# H3BR6_Hardware.net
KiCad netlist of a schematic drawn in EAGLE
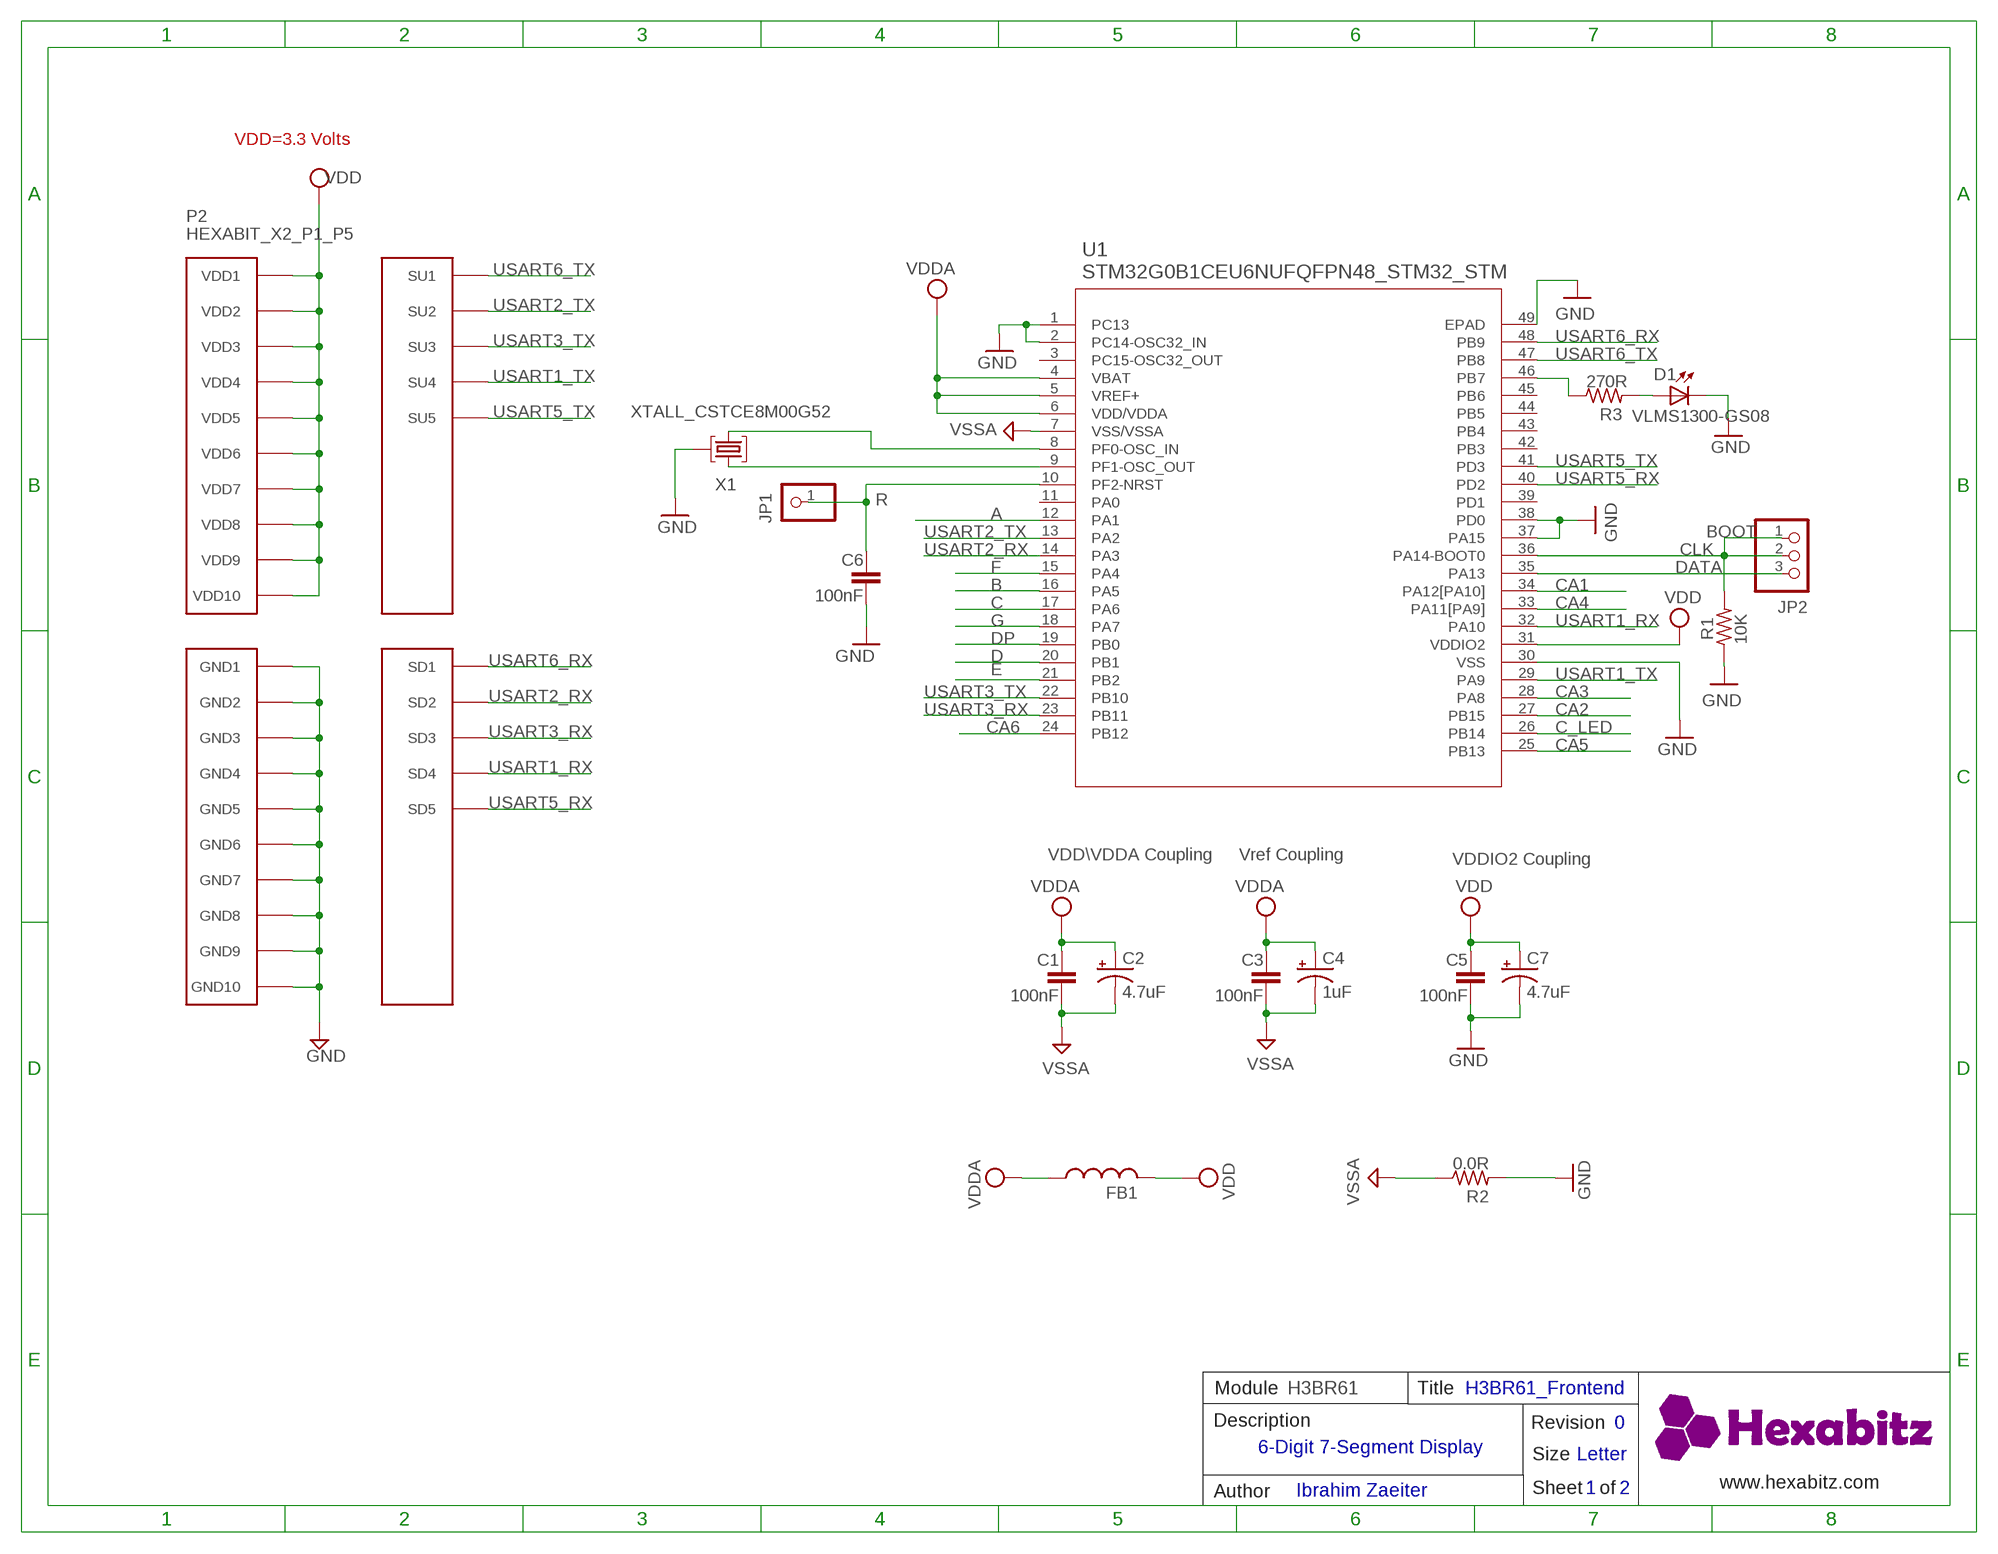
[diagram p0: schematic, sheet 1]
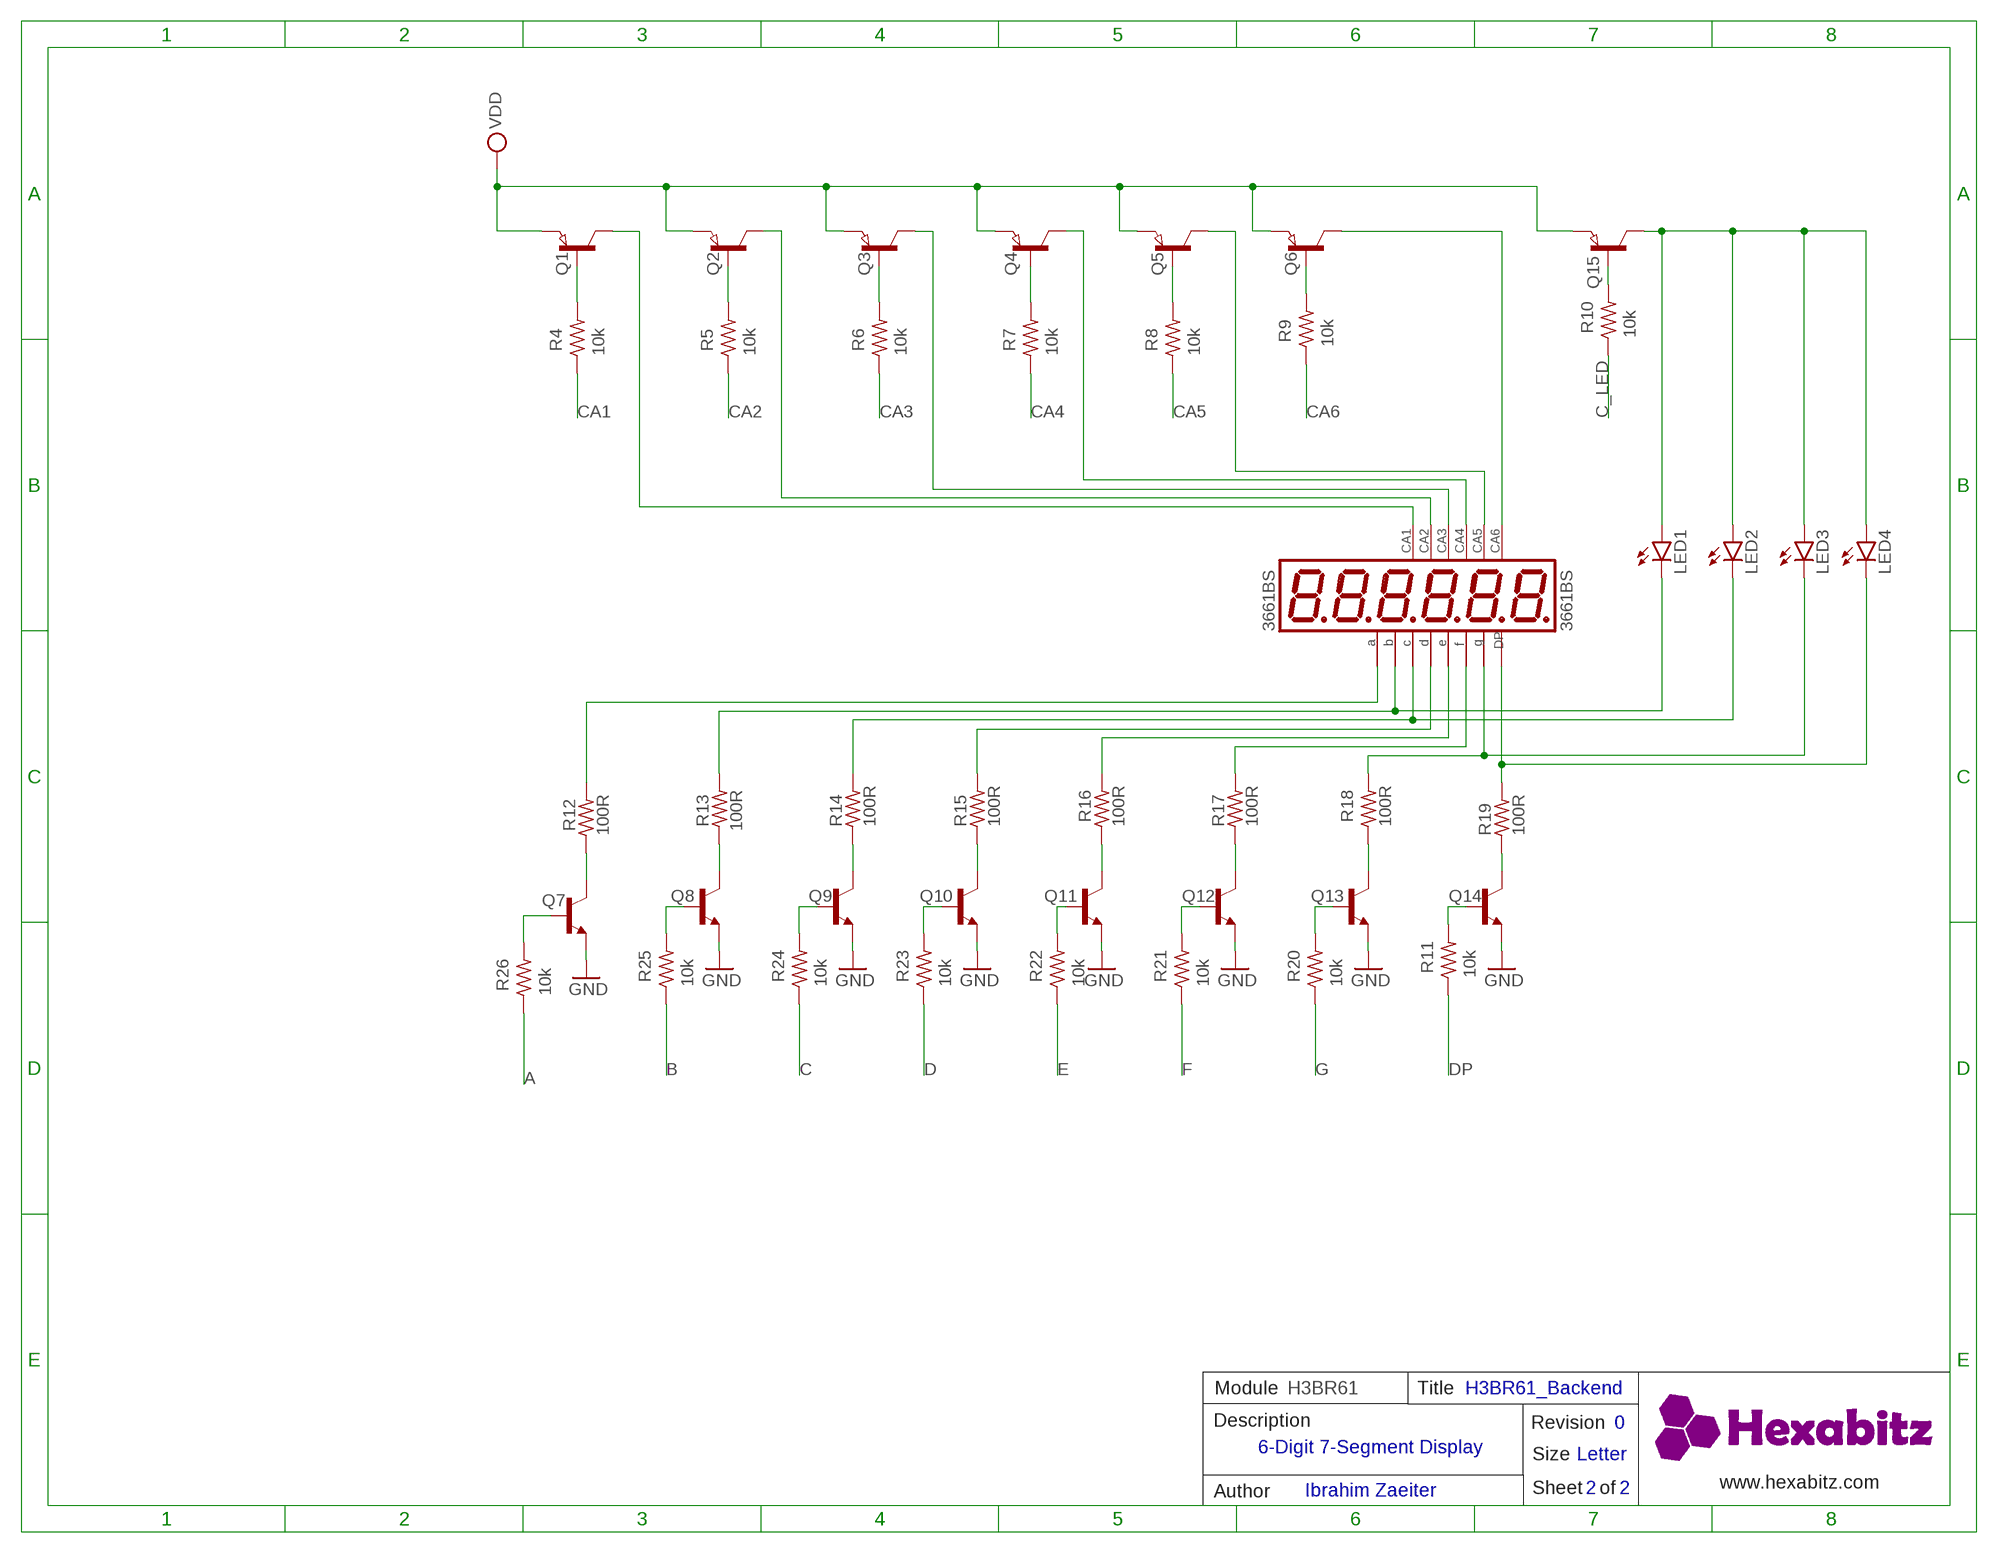
[diagram p1: schematic, sheet 2]

(export (version "E")
  (design (tool "Eeschema 10.0.6"))
  (components
    (comp (ref "3661BS")
      (value "3661BS")
      (footprint "eagle-import:3661BS")
      (libsource (lib "eagle-import") (part "3661BS"))
    )
    (comp (ref "LED1")
      (value "LED3MM")
      (footprint "eagle-import:LED3MM")
      (libsource (lib "eagle-import") (part "LED3MM"))
    )
    (comp (ref "LED2")
      (value "LED3MM")
      (footprint "eagle-import:LED3MM")
      (libsource (lib "eagle-import") (part "LED3MM"))
    )
    (comp (ref "LED3")
      (value "LED3MM")
      (footprint "eagle-import:LED3MM")
      (libsource (lib "eagle-import") (part "LED3MM"))
    )
    (comp (ref "LED4")
      (value "LED3MM")
      (footprint "eagle-import:LED3MM")
      (libsource (lib "eagle-import") (part "LED3MM"))
    )
    (comp (ref "Q1")
      (value "SEMICON-SMD-IPC_PNP-TRANSISTOR_SOT23")
      (footprint "eagle-import:SEMICON-SMD-IPC_SOT23")
      (libsource (lib "eagle-import") (part "SEMICON-SMD-IPC_PNP-TRANSISTOR_SOT23"))
    )
    (comp (ref "Q2")
      (value "SEMICON-SMD-IPC_PNP-TRANSISTOR_SOT23")
      (footprint "eagle-import:SEMICON-SMD-IPC_SOT23")
      (libsource (lib "eagle-import") (part "SEMICON-SMD-IPC_PNP-TRANSISTOR_SOT23"))
    )
    (comp (ref "Q3")
      (value "SEMICON-SMD-IPC_PNP-TRANSISTOR_SOT23")
      (footprint "eagle-import:SEMICON-SMD-IPC_SOT23")
      (libsource (lib "eagle-import") (part "SEMICON-SMD-IPC_PNP-TRANSISTOR_SOT23"))
    )
    (comp (ref "Q4")
      (value "SEMICON-SMD-IPC_PNP-TRANSISTOR_SOT23")
      (footprint "eagle-import:SEMICON-SMD-IPC_SOT23")
      (libsource (lib "eagle-import") (part "SEMICON-SMD-IPC_PNP-TRANSISTOR_SOT23"))
    )
    (comp (ref "Q5")
      (value "SEMICON-SMD-IPC_PNP-TRANSISTOR_SOT23")
      (footprint "eagle-import:SEMICON-SMD-IPC_SOT23")
      (libsource (lib "eagle-import") (part "SEMICON-SMD-IPC_PNP-TRANSISTOR_SOT23"))
    )
    (comp (ref "Q6")
      (value "SEMICON-SMD-IPC_PNP-TRANSISTOR_SOT23")
      (footprint "eagle-import:SEMICON-SMD-IPC_SOT23")
      (libsource (lib "eagle-import") (part "SEMICON-SMD-IPC_PNP-TRANSISTOR_SOT23"))
    )
    (comp (ref "Q7")
      (value "MMBT3904LT1")
      (footprint "eagle-import:MMBT3904LT1")
      (libsource (lib "eagle-import") (part "MMBT3904LT1"))
    )
    (comp (ref "Q8")
      (value "MMBT3904LT1")
      (footprint "eagle-import:MMBT3904LT1")
      (libsource (lib "eagle-import") (part "MMBT3904LT1"))
    )
    (comp (ref "Q9")
      (value "MMBT3904LT1")
      (footprint "eagle-import:MMBT3904LT1")
      (libsource (lib "eagle-import") (part "MMBT3904LT1"))
    )
    (comp (ref "Q10")
      (value "MMBT3904LT1")
      (footprint "eagle-import:MMBT3904LT1")
      (libsource (lib "eagle-import") (part "MMBT3904LT1"))
    )
    (comp (ref "Q11")
      (value "MMBT3904LT1")
      (footprint "eagle-import:MMBT3904LT1")
      (libsource (lib "eagle-import") (part "MMBT3904LT1"))
    )
    (comp (ref "Q12")
      (value "MMBT3904LT1")
      (footprint "eagle-import:MMBT3904LT1")
      (libsource (lib "eagle-import") (part "MMBT3904LT1"))
    )
    (comp (ref "Q13")
      (value "MMBT3904LT1")
      (footprint "eagle-import:MMBT3904LT1")
      (libsource (lib "eagle-import") (part "MMBT3904LT1"))
    )
    (comp (ref "Q14")
      (value "MMBT3904LT1")
      (footprint "eagle-import:MMBT3904LT1")
      (libsource (lib "eagle-import") (part "MMBT3904LT1"))
    )
    (comp (ref "Q15")
      (value "SEMICON-SMD-IPC_PNP-TRANSISTOR_SOT23")
      (footprint "eagle-import:SEMICON-SMD-IPC_SOT23")
      (libsource (lib "eagle-import") (part "SEMICON-SMD-IPC_PNP-TRANSISTOR_SOT23"))
    )
    (comp (ref "R4")
      (value "10k")
      (footprint "eagle-import:R-0603")
      (libsource (lib "eagle-import") (part "R-0603"))
    )
    (comp (ref "R5")
      (value "10k")
      (footprint "eagle-import:R-0603")
      (libsource (lib "eagle-import") (part "R-0603"))
    )
    (comp (ref "R6")
      (value "10k")
      (footprint "eagle-import:R-0603")
      (libsource (lib "eagle-import") (part "R-0603"))
    )
    (comp (ref "R7")
      (value "10k")
      (footprint "eagle-import:R-0603")
      (libsource (lib "eagle-import") (part "R-0603"))
    )
    (comp (ref "R8")
      (value "10k")
      (footprint "eagle-import:R-0603")
      (libsource (lib "eagle-import") (part "R-0603"))
    )
    (comp (ref "R9")
      (value "10k")
      (footprint "eagle-import:R-0603")
      (libsource (lib "eagle-import") (part "R-0603"))
    )
    (comp (ref "R10")
      (value "10k")
      (footprint "eagle-import:R-0603")
      (libsource (lib "eagle-import") (part "R-0603"))
    )
    (comp (ref "R11")
      (value "10k")
      (footprint "eagle-import:R-0603")
      (libsource (lib "eagle-import") (part "R-0603"))
    )
    (comp (ref "R12")
      (value "100R")
      (footprint "eagle-import:R-0603")
      (libsource (lib "eagle-import") (part "R-0603"))
    )
    (comp (ref "R13")
      (value "100R")
      (footprint "eagle-import:R-0603")
      (libsource (lib "eagle-import") (part "R-0603"))
    )
    (comp (ref "R14")
      (value "100R")
      (footprint "eagle-import:R-0603")
      (libsource (lib "eagle-import") (part "R-0603"))
    )
    (comp (ref "R15")
      (value "100R")
      (footprint "eagle-import:R-0603")
      (libsource (lib "eagle-import") (part "R-0603"))
    )
    (comp (ref "R16")
      (value "100R")
      (footprint "eagle-import:R-0603")
      (libsource (lib "eagle-import") (part "R-0603"))
    )
    (comp (ref "R17")
      (value "100R")
      (footprint "eagle-import:R-0603")
      (libsource (lib "eagle-import") (part "R-0603"))
    )
    (comp (ref "R18")
      (value "100R")
      (footprint "eagle-import:R-0603")
      (libsource (lib "eagle-import") (part "R-0603"))
    )
    (comp (ref "R19")
      (value "100R")
      (footprint "eagle-import:R-0603")
      (libsource (lib "eagle-import") (part "R-0603"))
    )
    (comp (ref "R20")
      (value "10k")
      (footprint "eagle-import:R-0603")
      (libsource (lib "eagle-import") (part "R-0603"))
    )
    (comp (ref "R21")
      (value "10k")
      (footprint "eagle-import:R-0603")
      (libsource (lib "eagle-import") (part "R-0603"))
    )
    (comp (ref "R22")
      (value "10k")
      (footprint "eagle-import:R-0603")
      (libsource (lib "eagle-import") (part "R-0603"))
    )
    (comp (ref "R23")
      (value "10k")
      (footprint "eagle-import:R-0603")
      (libsource (lib "eagle-import") (part "R-0603"))
    )
    (comp (ref "R24")
      (value "10k")
      (footprint "eagle-import:R-0603")
      (libsource (lib "eagle-import") (part "R-0603"))
    )
    (comp (ref "R25")
      (value "10k")
      (footprint "eagle-import:R-0603")
      (libsource (lib "eagle-import") (part "R-0603"))
    )
    (comp (ref "R26")
      (value "10k")
      (footprint "eagle-import:R-0603")
      (libsource (lib "eagle-import") (part "R-0603"))
    )
    (comp (ref "C1")
      (value "100nF")
      (footprint "eagle-import:C-0603")
      (libsource (lib "eagle-import") (part "C-0603"))
    )
    (comp (ref "C2")
      (value "4.7uF")
      (footprint "eagle-import:C-0805-POL")
      (libsource (lib "eagle-import") (part "C-0805-POL"))
    )
    (comp (ref "C3")
      (value "100nF")
      (footprint "eagle-import:C-0603")
      (libsource (lib "eagle-import") (part "C-0603"))
    )
    (comp (ref "C4")
      (value "1uF")
      (footprint "eagle-import:C-0805-POL")
      (libsource (lib "eagle-import") (part "C-0805-POL"))
    )
    (comp (ref "C5")
      (value "100nF")
      (footprint "eagle-import:C-0603")
      (libsource (lib "eagle-import") (part "C-0603"))
    )
    (comp (ref "C6")
      (value "100nF")
      (footprint "eagle-import:C-0603")
      (libsource (lib "eagle-import") (part "C-0603"))
    )
    (comp (ref "C7")
      (value "4.7uF")
      (footprint "eagle-import:C-0805-POL")
      (libsource (lib "eagle-import") (part "C-0805-POL"))
    )
    (comp (ref "D1")
      (value "VLMS1300-GS08")
      (footprint "eagle-import:VLMS1300-GS08")
      (fields
        (field (name "MFN") "Vishay")
        (field (name "MPN") "VLMS1300-GS08")
        (field (name "OCTOPART_URL") "https://octopart.com/vlms1300-gs08-vishay-21709201?r=sp&s=_gcP4_q8T1SC6PJQPTQ9yA")
      )
      (libsource (lib "eagle-import") (part "VLMS1300-GS08"))
    )
    (comp (ref "FB1")
      (value "FB-0603")
      (footprint "eagle-import:FB-0603")
      (libsource (lib "eagle-import") (part "FB-0603"))
    )
    (comp (ref "JP1")
      (value "R")
      (footprint "eagle-import:1X01")
      (fields (field (name "MPN") "87227-1"))
      (libsource (lib "eagle-import") (part "PINHD-1X1"))
    )
    (comp (ref "JP2")
      (value "PINHD-1X3")
      (footprint "eagle-import:1X03")
      (libsource (lib "eagle-import") (part "PINHD-1X3"))
    )
    (comp (ref "P2")
      (value "HEXABIT_X2_P1_P5")
      (footprint "eagle-import:HEXABIT_17.32_X2_P1_P5")
      (libsource (lib "eagle-import") (part "HEXABIT_X2_P1_P5"))
    )
    (comp (ref "R1")
      (value "10K")
      (footprint "eagle-import:R-0603")
      (libsource (lib "eagle-import") (part "R-0603"))
    )
    (comp (ref "R2")
      (value "0.0R")
      (footprint "eagle-import:R-0603")
      (libsource (lib "eagle-import") (part "R-0603"))
    )
    (comp (ref "R3")
      (value "270R")
      (footprint "eagle-import:R-0603")
      (libsource (lib "eagle-import") (part "R-0603"))
    )
    (comp (ref "U1")
      (value "STM32G0B1CEU6NUFQFPN48_STM32_STM")
      (footprint "eagle-import:UFQFPN48_STM32_STM")
      (fields
        (field (name "MPN") "STM32G0B1CEU6N")
        (field (name "COPYRIGHT") "Copyright (C) 2022 Ultra Librarian. All rights reserved.")
      )
      (libsource (lib "eagle-import") (part "STM32G0B1CEU6NUFQFPN48_STM32_STM"))
    )
    (comp (ref "X1")
      (value "XTALL_CSTCE8M00G52")
      (footprint "eagle-import:XTALL_CSTCE8M00G52")
      (fields (field (name "MPN") "CSTCE8M00G52Z-R0"))
      (libsource (lib "eagle-import") (part "XTALL_CSTCE8M00G52"))
    )
  )
  (nets
    (net (code "1") (name "A") (class "Default")
      (node (ref "R26") (pin "1") (pinfunction "1_1") (pintype "passive"))
      (node (ref "U1") (pin "12") (pinfunction "PA1_12") (pintype "bidirectional"))
    )
    (net (code "2") (name "B") (class "Default")
      (node (ref "R25") (pin "1") (pinfunction "1_1") (pintype "passive"))
      (node (ref "U1") (pin "16") (pinfunction "PA5_16") (pintype "bidirectional"))
    )
    (net (code "3") (name "C") (class "Default")
      (node (ref "R24") (pin "1") (pinfunction "1_1") (pintype "passive"))
      (node (ref "U1") (pin "17") (pinfunction "PA6_17") (pintype "bidirectional"))
    )
    (net (code "4") (name "CA1") (class "Default")
      (node (ref "R4") (pin "1") (pinfunction "1_1") (pintype "passive"))
      (node (ref "U1") (pin "34") (pinfunction "PA12[PA10]_34") (pintype "bidirectional"))
    )
    (net (code "5") (name "CA2") (class "Default")
      (node (ref "R5") (pin "1") (pinfunction "1_1") (pintype "passive"))
      (node (ref "U1") (pin "27") (pinfunction "PB15_27") (pintype "bidirectional"))
    )
    (net (code "6") (name "CA3") (class "Default")
      (node (ref "R6") (pin "1") (pinfunction "1_1") (pintype "passive"))
      (node (ref "U1") (pin "28") (pinfunction "PA8_28") (pintype "bidirectional"))
    )
    (net (code "7") (name "CA4") (class "Default")
      (node (ref "R7") (pin "1") (pinfunction "1_1") (pintype "passive"))
      (node (ref "U1") (pin "33") (pinfunction "PA11[PA9]_33") (pintype "bidirectional"))
    )
    (net (code "8") (name "CA5") (class "Default")
      (node (ref "R8") (pin "1") (pinfunction "1_1") (pintype "passive"))
      (node (ref "U1") (pin "25") (pinfunction "PB13_25") (pintype "bidirectional"))
    )
    (net (code "9") (name "CA6") (class "Default")
      (node (ref "R9") (pin "1") (pinfunction "1_1") (pintype "passive"))
      (node (ref "U1") (pin "24") (pinfunction "PB12_24") (pintype "bidirectional"))
    )
    (net (code "10") (name "CLK") (class "Default")
      (node (ref "JP2") (pin "1") (pinfunction "1_1") (pintype "passive"))
      (node (ref "JP2") (pin "2") (pinfunction "2_2") (pintype "passive"))
      (node (ref "R1") (pin "2") (pinfunction "2_2") (pintype "passive"))
      (node (ref "U1") (pin "36") (pinfunction "PA14-BOOT0_36") (pintype "bidirectional"))
    )
    (net (code "11") (name "C_LED") (class "Default")
      (node (ref "R10") (pin "1") (pinfunction "1_1") (pintype "passive"))
      (node (ref "U1") (pin "26") (pinfunction "PB14_26") (pintype "bidirectional"))
    )
    (net (code "12") (name "D") (class "Default")
      (node (ref "R23") (pin "1") (pinfunction "1_1") (pintype "passive"))
      (node (ref "U1") (pin "20") (pinfunction "PB1_20") (pintype "bidirectional"))
    )
    (net (code "13") (name "DATA") (class "Default")
      (node (ref "JP2") (pin "3") (pinfunction "3_3") (pintype "passive"))
      (node (ref "U1") (pin "35") (pinfunction "PA13_35") (pintype "bidirectional"))
    )
    (net (code "14") (name "DP") (class "Default")
      (node (ref "R11") (pin "1") (pinfunction "1_1") (pintype "passive"))
      (node (ref "U1") (pin "19") (pinfunction "PB0_19") (pintype "bidirectional"))
    )
    (net (code "15") (name "E") (class "Default")
      (node (ref "R22") (pin "1") (pinfunction "1_1") (pintype "passive"))
      (node (ref "U1") (pin "21") (pinfunction "PB2_21") (pintype "bidirectional"))
    )
    (net (code "16") (name "F") (class "Default")
      (node (ref "R21") (pin "1") (pinfunction "1_1") (pintype "passive"))
      (node (ref "U1") (pin "15") (pinfunction "PA4_15") (pintype "bidirectional"))
    )
    (net (code "17") (name "G") (class "Default")
      (node (ref "R20") (pin "1") (pinfunction "1_1") (pintype "passive"))
      (node (ref "U1") (pin "18") (pinfunction "PA7_18") (pintype "bidirectional"))
    )
    (net (code "18") (name "GND") (class "Default")
      (node (ref "C5") (pin "2") (pinfunction "2_2") (pintype "passive"))
      (node (ref "C6") (pin "2") (pinfunction "2_2") (pintype "passive"))
      (node (ref "C7") (pin "2") (pinfunction "-_2") (pintype "passive"))
      (node (ref "D1") (pin "C") (pinfunction "C_C") (pintype "passive"))
      (node (ref "P2") (pin "PAD_PD11") (pinfunction "GND1_PAD_PD11") (pintype "power_in"))
      (node (ref "P2") (pin "PAD_PD12") (pinfunction "GND2_PAD_PD12") (pintype "power_in"))
      (node (ref "P2") (pin "PAD_PD13") (pinfunction "GND3_PAD_PD13") (pintype "power_in"))
      (node (ref "P2") (pin "PAD_PD14") (pinfunction "GND4_PAD_PD14") (pintype "power_in"))
      (node (ref "P2") (pin "PAD_PD15") (pinfunction "GND5_PAD_PD15") (pintype "power_in"))
      (node (ref "P2") (pin "PAD_PD16") (pinfunction "GND6_PAD_PD16") (pintype "power_in"))
      (node (ref "P2") (pin "PAD_PD17") (pinfunction "GND7_PAD_PD17") (pintype "power_in"))
      (node (ref "P2") (pin "PAD_PD18") (pinfunction "GND8_PAD_PD18") (pintype "power_in"))
      (node (ref "P2") (pin "PAD_PD19") (pinfunction "GND9_PAD_PD19") (pintype "power_in"))
      (node (ref "P2") (pin "PAD_PD20") (pinfunction "GND10_PAD_PD20") (pintype "power_in"))
      (node (ref "Q10") (pin "2") (pinfunction "E_2") (pintype "passive"))
      (node (ref "Q11") (pin "2") (pinfunction "E_2") (pintype "passive"))
      (node (ref "Q12") (pin "2") (pinfunction "E_2") (pintype "passive"))
      (node (ref "Q13") (pin "2") (pinfunction "E_2") (pintype "passive"))
      (node (ref "Q14") (pin "2") (pinfunction "E_2") (pintype "passive"))
      (node (ref "Q7") (pin "2") (pinfunction "E_2") (pintype "passive"))
      (node (ref "Q8") (pin "2") (pinfunction "E_2") (pintype "passive"))
      (node (ref "Q9") (pin "2") (pinfunction "E_2") (pintype "passive"))
      (node (ref "R1") (pin "1") (pinfunction "1_1") (pintype "passive"))
      (node (ref "R2") (pin "2") (pinfunction "2_2") (pintype "passive"))
      (node (ref "U1") (pin "1") (pinfunction "PC13_1") (pintype "bidirectional"))
      (node (ref "U1") (pin "2") (pinfunction "PC14-OSC32_IN_2") (pintype "bidirectional"))
      (node (ref "U1") (pin "30") (pinfunction "VSS_30") (pintype "passive"))
      (node (ref "U1") (pin "37") (pinfunction "PA15_37") (pintype "bidirectional"))
      (node (ref "U1") (pin "38") (pinfunction "PD0_38") (pintype "bidirectional"))
      (node (ref "U1") (pin "49") (pinfunction "EPAD_49") (pintype "passive"))
      (node (ref "X1") (pin "P$2") (pinfunction "2_P$2") (pintype "passive"))
    )
    (net (code "19") (name "Net-(3661BS-A)") (class "Default")
      (node (ref "3661BS") (pin "13") (pinfunction "A_13") (pintype "passive"))
      (node (ref "R12") (pin "2") (pinfunction "2_2") (pintype "passive"))
    )
    (net (code "20") (name "Net-(3661BS-B)") (class "Default")
      (node (ref "3661BS") (pin "9") (pinfunction "B_9") (pintype "passive"))
      (node (ref "LED1") (pin "K") (pinfunction "C_K") (pintype "passive"))
      (node (ref "R13") (pin "2") (pinfunction "2_2") (pintype "passive"))
    )
    (net (code "21") (name "Net-(3661BS-C)") (class "Default")
      (node (ref "3661BS") (pin "4") (pinfunction "C_4") (pintype "passive"))
      (node (ref "LED2") (pin "K") (pinfunction "C_K") (pintype "passive"))
      (node (ref "R14") (pin "2") (pinfunction "2_2") (pintype "passive"))
    )
    (net (code "22") (name "Net-(3661BS-D)") (class "Default")
      (node (ref "3661BS") (pin "2") (pinfunction "D_2") (pintype "passive"))
      (node (ref "R15") (pin "2") (pinfunction "2_2") (pintype "passive"))
    )
    (net (code "23") (name "Net-(3661BS-DP)") (class "Default")
      (node (ref "3661BS") (pin "3") (pinfunction "DP_3") (pintype "passive"))
      (node (ref "LED4") (pin "K") (pinfunction "C_K") (pintype "passive"))
      (node (ref "R19") (pin "2") (pinfunction "2_2") (pintype "passive"))
    )
    (net (code "24") (name "Net-(3661BS-E)") (class "Default")
      (node (ref "3661BS") (pin "1") (pinfunction "E_1") (pintype "passive"))
      (node (ref "R16") (pin "2") (pinfunction "2_2") (pintype "passive"))
    )
    (net (code "25") (name "Net-(3661BS-F)") (class "Default")
      (node (ref "3661BS") (pin "12") (pinfunction "F_12") (pintype "passive"))
      (node (ref "R17") (pin "2") (pinfunction "2_2") (pintype "passive"))
    )
    (net (code "26") (name "Net-(3661BS-G)") (class "Default")
      (node (ref "3661BS") (pin "5") (pinfunction "G_5") (pintype "passive"))
      (node (ref "LED3") (pin "K") (pinfunction "C_K") (pintype "passive"))
      (node (ref "R18") (pin "2") (pinfunction "2_2") (pintype "passive"))
    )
    (net (code "27") (name "Net-(D1-PadA)") (class "Default")
      (node (ref "D1") (pin "A") (pinfunction "A_A") (pintype "passive"))
      (node (ref "R3") (pin "2") (pinfunction "2_2") (pintype "passive"))
    )
    (net (code "28") (name "Net-(Q1-B)") (class "Default")
      (node (ref "Q1") (pin "1") (pinfunction "B_1") (pintype "passive"))
      (node (ref "R4") (pin "2") (pinfunction "2_2") (pintype "passive"))
    )
    (net (code "29") (name "Net-(Q1-C)") (class "Default")
      (node (ref "3661BS") (pin "14") (pinfunction "CA_14") (pintype "passive"))
      (node (ref "Q1") (pin "3") (pinfunction "C_3") (pintype "passive"))
    )
    (net (code "30") (name "Net-(Q2-B)") (class "Default")
      (node (ref "Q2") (pin "1") (pinfunction "B_1") (pintype "passive"))
      (node (ref "R5") (pin "2") (pinfunction "2_2") (pintype "passive"))
    )
    (net (code "31") (name "Net-(Q2-C)") (class "Default")
      (node (ref "3661BS") (pin "11") (pinfunction "CA_11") (pintype "passive"))
      (node (ref "Q2") (pin "3") (pinfunction "C_3") (pintype "passive"))
    )
    (net (code "32") (name "Net-(Q3-B)") (class "Default")
      (node (ref "Q3") (pin "1") (pinfunction "B_1") (pintype "passive"))
      (node (ref "R6") (pin "2") (pinfunction "2_2") (pintype "passive"))
    )
    (net (code "33") (name "Net-(Q3-C)") (class "Default")
      (node (ref "3661BS") (pin "10") (pinfunction "CA_10") (pintype "passive"))
      (node (ref "Q3") (pin "3") (pinfunction "C_3") (pintype "passive"))
    )
    (net (code "34") (name "Net-(Q4-B)") (class "Default")
      (node (ref "Q4") (pin "1") (pinfunction "B_1") (pintype "passive"))
      (node (ref "R7") (pin "2") (pinfunction "2_2") (pintype "passive"))
    )
    (net (code "35") (name "Net-(Q4-C)") (class "Default")
      (node (ref "3661BS") (pin "8") (pinfunction "CA_8") (pintype "passive"))
      (node (ref "Q4") (pin "3") (pinfunction "C_3") (pintype "passive"))
    )
    (net (code "36") (name "Net-(Q5-B)") (class "Default")
      (node (ref "Q5") (pin "1") (pinfunction "B_1") (pintype "passive"))
      (node (ref "R8") (pin "2") (pinfunction "2_2") (pintype "passive"))
    )
    (net (code "37") (name "Net-(Q5-C)") (class "Default")
      (node (ref "3661BS") (pin "6") (pinfunction "CA_6") (pintype "passive"))
      (node (ref "Q5") (pin "3") (pinfunction "C_3") (pintype "passive"))
    )
    (net (code "38") (name "Net-(Q6-B)") (class "Default")
      (node (ref "Q6") (pin "1") (pinfunction "B_1") (pintype "passive"))
      (node (ref "R9") (pin "2") (pinfunction "2_2") (pintype "passive"))
    )
    (net (code "39") (name "Net-(Q6-C)") (class "Default")
      (node (ref "3661BS") (pin "7") (pinfunction "CA_7") (pintype "passive"))
      (node (ref "Q6") (pin "3") (pinfunction "C_3") (pintype "passive"))
    )
    (net (code "40") (name "Net-(Q7-B)") (class "Default")
      (node (ref "Q7") (pin "1") (pinfunction "B_1") (pintype "passive"))
      (node (ref "R26") (pin "2") (pinfunction "2_2") (pintype "passive"))
    )
    (net (code "41") (name "Net-(Q7-C)") (class "Default")
      (node (ref "Q7") (pin "3") (pinfunction "C_3") (pintype "passive"))
      (node (ref "R12") (pin "1") (pinfunction "1_1") (pintype "passive"))
    )
    (net (code "42") (name "Net-(Q8-B)") (class "Default")
      (node (ref "Q8") (pin "1") (pinfunction "B_1") (pintype "passive"))
      (node (ref "R25") (pin "2") (pinfunction "2_2") (pintype "passive"))
    )
    (net (code "43") (name "Net-(Q8-C)") (class "Default")
      (node (ref "Q8") (pin "3") (pinfunction "C_3") (pintype "passive"))
      (node (ref "R13") (pin "1") (pinfunction "1_1") (pintype "passive"))
    )
    (net (code "44") (name "Net-(Q9-B)") (class "Default")
      (node (ref "Q9") (pin "1") (pinfunction "B_1") (pintype "passive"))
      (node (ref "R24") (pin "2") (pinfunction "2_2") (pintype "passive"))
    )
    (net (code "45") (name "Net-(Q9-C)") (class "Default")
      (node (ref "Q9") (pin "3") (pinfunction "C_3") (pintype "passive"))
      (node (ref "R14") (pin "1") (pinfunction "1_1") (pintype "passive"))
    )
    (net (code "46") (name "Net-(Q10-B)") (class "Default")
      (node (ref "Q10") (pin "1") (pinfunction "B_1") (pintype "passive"))
      (node (ref "R23") (pin "2") (pinfunction "2_2") (pintype "passive"))
    )
    (net (code "47") (name "Net-(Q10-C)") (class "Default")
      (node (ref "Q10") (pin "3") (pinfunction "C_3") (pintype "passive"))
      (node (ref "R15") (pin "1") (pinfunction "1_1") (pintype "passive"))
    )
    (net (code "48") (name "Net-(Q11-B)") (class "Default")
      (node (ref "Q11") (pin "1") (pinfunction "B_1") (pintype "passive"))
      (node (ref "R22") (pin "2") (pinfunction "2_2") (pintype "passive"))
    )
    (net (code "49") (name "Net-(Q11-C)") (class "Default")
      (node (ref "Q11") (pin "3") (pinfunction "C_3") (pintype "passive"))
      (node (ref "R16") (pin "1") (pinfunction "1_1") (pintype "passive"))
    )
    (net (code "50") (name "Net-(Q12-B)") (class "Default")
      (node (ref "Q12") (pin "1") (pinfunction "B_1") (pintype "passive"))
      (node (ref "R21") (pin "2") (pinfunction "2_2") (pintype "passive"))
    )
    (net (code "51") (name "Net-(Q12-C)") (class "Default")
      (node (ref "Q12") (pin "3") (pinfunction "C_3") (pintype "passive"))
      (node (ref "R17") (pin "1") (pinfunction "1_1") (pintype "passive"))
    )
    (net (code "52") (name "Net-(Q13-B)") (class "Default")
      (node (ref "Q13") (pin "1") (pinfunction "B_1") (pintype "passive"))
      (node (ref "R20") (pin "2") (pinfunction "2_2") (pintype "passive"))
    )
    (net (code "53") (name "Net-(Q13-C)") (class "Default")
      (node (ref "Q13") (pin "3") (pinfunction "C_3") (pintype "passive"))
      (node (ref "R18") (pin "1") (pinfunction "1_1") (pintype "passive"))
    )
    (net (code "54") (name "Net-(Q14-B)") (class "Default")
      (node (ref "Q14") (pin "1") (pinfunction "B_1") (pintype "passive"))
      (node (ref "R11") (pin "2") (pinfunction "2_2") (pintype "passive"))
    )
    (net (code "55") (name "Net-(Q14-C)") (class "Default")
      (node (ref "Q14") (pin "3") (pinfunction "C_3") (pintype "passive"))
      (node (ref "R19") (pin "1") (pinfunction "1_1") (pintype "passive"))
    )
    (net (code "56") (name "Net-(Q15-B)") (class "Default")
      (node (ref "Q15") (pin "1") (pinfunction "B_1") (pintype "passive"))
      (node (ref "R10") (pin "2") (pinfunction "2_2") (pintype "passive"))
    )
    (net (code "57") (name "Net-(Q15-C)") (class "Default")
      (node (ref "LED1") (pin "A") (pinfunction "A_A") (pintype "passive"))
      (node (ref "LED2") (pin "A") (pinfunction "A_A") (pintype "passive"))
      (node (ref "LED3") (pin "A") (pinfunction "A_A") (pintype "passive"))
      (node (ref "LED4") (pin "A") (pinfunction "A_A") (pintype "passive"))
      (node (ref "Q15") (pin "3") (pinfunction "C_3") (pintype "passive"))
    )
    (net (code "58") (name "Net-(U1-PB7)") (class "Default")
      (node (ref "R3") (pin "1") (pinfunction "1_1") (pintype "passive"))
      (node (ref "U1") (pin "46") (pinfunction "PB7_46") (pintype "bidirectional"))
    )
    (net (code "59") (name "Net-(U1-PF0-OSC_IN)") (class "Default")
      (node (ref "U1") (pin "8") (pinfunction "PF0-OSC_IN_8") (pintype "bidirectional"))
      (node (ref "X1") (pin "P$3") (pinfunction "3_P$3") (pintype "passive"))
    )
    (net (code "60") (name "Net-(U1-PF1-OSC_OUT)") (class "Default")
      (node (ref "U1") (pin "9") (pinfunction "PF1-OSC_OUT_9") (pintype "bidirectional"))
      (node (ref "X1") (pin "P$1") (pinfunction "1_P$1") (pintype "passive"))
    )
    (net (code "61") (name "Net-(U1-PF2-NRST)") (class "Default")
      (node (ref "C6") (pin "1") (pinfunction "1_1") (pintype "passive"))
      (node (ref "JP1") (pin "1") (pinfunction "1_1") (pintype "passive"))
      (node (ref "U1") (pin "10") (pinfunction "PF2-NRST_10") (pintype "bidirectional"))
    )
    (net (code "62") (name "USART1_RX") (class "Default")
      (node (ref "P2") (pin "PAD_PD4") (pinfunction "SD4_PAD_PD4") (pintype "bidirectional"))
      (node (ref "U1") (pin "32") (pinfunction "PA10_32") (pintype "bidirectional"))
    )
    (net (code "63") (name "USART1_TX") (class "Default")
      (node (ref "P2") (pin "PAD_PU4") (pinfunction "SU4_PAD_PU4") (pintype "bidirectional"))
      (node (ref "U1") (pin "29") (pinfunction "PA9_29") (pintype "bidirectional"))
    )
    (net (code "64") (name "USART2_RX") (class "Default")
      (node (ref "P2") (pin "PAD_PD2") (pinfunction "SD2_PAD_PD2") (pintype "bidirectional"))
      (node (ref "U1") (pin "14") (pinfunction "PA3_14") (pintype "bidirectional"))
    )
    (net (code "65") (name "USART2_TX") (class "Default")
      (node (ref "P2") (pin "PAD_PU2") (pinfunction "SU2_PAD_PU2") (pintype "bidirectional"))
      (node (ref "U1") (pin "13") (pinfunction "PA2_13") (pintype "bidirectional"))
    )
    (net (code "66") (name "USART3_RX") (class "Default")
      (node (ref "P2") (pin "PAD_PD3") (pinfunction "SD3_PAD_PD3") (pintype "bidirectional"))
      (node (ref "U1") (pin "23") (pinfunction "PB11_23") (pintype "bidirectional"))
    )
    (net (code "67") (name "USART3_TX") (class "Default")
      (node (ref "P2") (pin "PAD_PU3") (pinfunction "SU3_PAD_PU3") (pintype "bidirectional"))
      (node (ref "U1") (pin "22") (pinfunction "PB10_22") (pintype "bidirectional"))
    )
    (net (code "68") (name "USART5_RX") (class "Default")
      (node (ref "P2") (pin "PAD_PD5") (pinfunction "SD5_PAD_PD5") (pintype "bidirectional"))
      (node (ref "U1") (pin "40") (pinfunction "PD2_40") (pintype "bidirectional"))
    )
    (net (code "69") (name "USART5_TX") (class "Default")
      (node (ref "P2") (pin "PAD_PU5") (pinfunction "SU5_PAD_PU5") (pintype "bidirectional"))
      (node (ref "U1") (pin "41") (pinfunction "PD3_41") (pintype "bidirectional"))
    )
    (net (code "70") (name "USART6_RX") (class "Default")
      (node (ref "P2") (pin "PAD_PD1") (pinfunction "SD1_PAD_PD1") (pintype "bidirectional"))
      (node (ref "U1") (pin "48") (pinfunction "PB9_48") (pintype "bidirectional"))
    )
    (net (code "71") (name "USART6_TX") (class "Default")
      (node (ref "P2") (pin "PAD_PU1") (pinfunction "SU1_PAD_PU1") (pintype "bidirectional"))
      (node (ref "U1") (pin "47") (pinfunction "PB8_47") (pintype "bidirectional"))
    )
    (net (code "72") (name "VDD") (class "Default")
      (node (ref "C5") (pin "1") (pinfunction "1_1") (pintype "passive"))
      (node (ref "C7") (pin "1") (pinfunction "+_1") (pintype "passive"))
      (node (ref "FB1") (pin "2") (pinfunction "2_2") (pintype "passive"))
      (node (ref "P2") (pin "PAD_PU11") (pinfunction "VDD1_PAD_PU11") (pintype "power_in"))
      (node (ref "P2") (pin "PAD_PU12") (pinfunction "VDD2_PAD_PU12") (pintype "power_in"))
      (node (ref "P2") (pin "PAD_PU13") (pinfunction "VDD3_PAD_PU13") (pintype "power_in"))
      (node (ref "P2") (pin "PAD_PU14") (pinfunction "VDD4_PAD_PU14") (pintype "power_in"))
      (node (ref "P2") (pin "PAD_PU15") (pinfunction "VDD5_PAD_PU15") (pintype "power_in"))
      (node (ref "P2") (pin "PAD_PU16") (pinfunction "VDD6_PAD_PU16") (pintype "power_in"))
      (node (ref "P2") (pin "PAD_PU17") (pinfunction "VDD7_PAD_PU17") (pintype "power_in"))
      (node (ref "P2") (pin "PAD_PU18") (pinfunction "VDD8_PAD_PU18") (pintype "power_in"))
      (node (ref "P2") (pin "PAD_PU19") (pinfunction "VDD9_PAD_PU19") (pintype "power_in"))
      (node (ref "P2") (pin "PAD_PU20") (pinfunction "VDD10_PAD_PU20") (pintype "power_in"))
      (node (ref "Q1") (pin "2") (pinfunction "E_2") (pintype "passive"))
      (node (ref "Q15") (pin "2") (pinfunction "E_2") (pintype "passive"))
      (node (ref "Q2") (pin "2") (pinfunction "E_2") (pintype "passive"))
      (node (ref "Q3") (pin "2") (pinfunction "E_2") (pintype "passive"))
      (node (ref "Q4") (pin "2") (pinfunction "E_2") (pintype "passive"))
      (node (ref "Q5") (pin "2") (pinfunction "E_2") (pintype "passive"))
      (node (ref "Q6") (pin "2") (pinfunction "E_2") (pintype "passive"))
      (node (ref "U1") (pin "31") (pinfunction "VDDIO2_31") (pintype "power_in"))
    )
    (net (code "73") (name "VDDA") (class "Default")
      (node (ref "C1") (pin "1") (pinfunction "1_1") (pintype "passive"))
      (node (ref "C2") (pin "1") (pinfunction "+_1") (pintype "passive"))
      (node (ref "C3") (pin "1") (pinfunction "1_1") (pintype "passive"))
      (node (ref "C4") (pin "1") (pinfunction "+_1") (pintype "passive"))
      (node (ref "FB1") (pin "1") (pinfunction "1_1") (pintype "passive"))
      (node (ref "U1") (pin "4") (pinfunction "VBAT_4") (pintype "power_in"))
      (node (ref "U1") (pin "5") (pinfunction "VREF+_5") (pintype "power_in"))
      (node (ref "U1") (pin "6") (pinfunction "VDD/VDDA_6") (pintype "power_in"))
    )
    (net (code "74") (name "VSSA") (class "Default")
      (node (ref "C1") (pin "2") (pinfunction "2_2") (pintype "passive"))
      (node (ref "C2") (pin "2") (pinfunction "-_2") (pintype "passive"))
      (node (ref "C3") (pin "2") (pinfunction "2_2") (pintype "passive"))
      (node (ref "C4") (pin "2") (pinfunction "-_2") (pintype "passive"))
      (node (ref "R2") (pin "1") (pinfunction "1_1") (pintype "passive"))
      (node (ref "U1") (pin "7") (pinfunction "VSS/VSSA_7") (pintype "passive"))
    )
    (net (code "75") (name "unconnected-(U1-PA0-Pad11)") (class "Default")
      (node (ref "U1") (pin "11") (pinfunction "PA0_11") (pintype "bidirectional"))
    )
    (net (code "76") (name "unconnected-(U1-PB3-Pad42)") (class "Default")
      (node (ref "U1") (pin "42") (pinfunction "PB3_42") (pintype "bidirectional"))
    )
    (net (code "77") (name "unconnected-(U1-PB4-Pad43)") (class "Default")
      (node (ref "U1") (pin "43") (pinfunction "PB4_43") (pintype "bidirectional"))
    )
    (net (code "78") (name "unconnected-(U1-PB5-Pad44)") (class "Default")
      (node (ref "U1") (pin "44") (pinfunction "PB5_44") (pintype "bidirectional"))
    )
    (net (code "79") (name "unconnected-(U1-PB6-Pad45)") (class "Default")
      (node (ref "U1") (pin "45") (pinfunction "PB6_45") (pintype "bidirectional"))
    )
    (net (code "80") (name "unconnected-(U1-PC15-OSC32_OUT-Pad3)") (class "Default")
      (node (ref "U1") (pin "3") (pinfunction "PC15-OSC32_OUT_3") (pintype "bidirectional"))
    )
    (net (code "81") (name "unconnected-(U1-PD1-Pad39)") (class "Default")
      (node (ref "U1") (pin "39") (pinfunction "PD1_39") (pintype "bidirectional"))
    )
  )
)
